# qfn-10-socket-pcb-mk-2_0_0.net
KiCad netlist of a schematic drawn in EAGLE
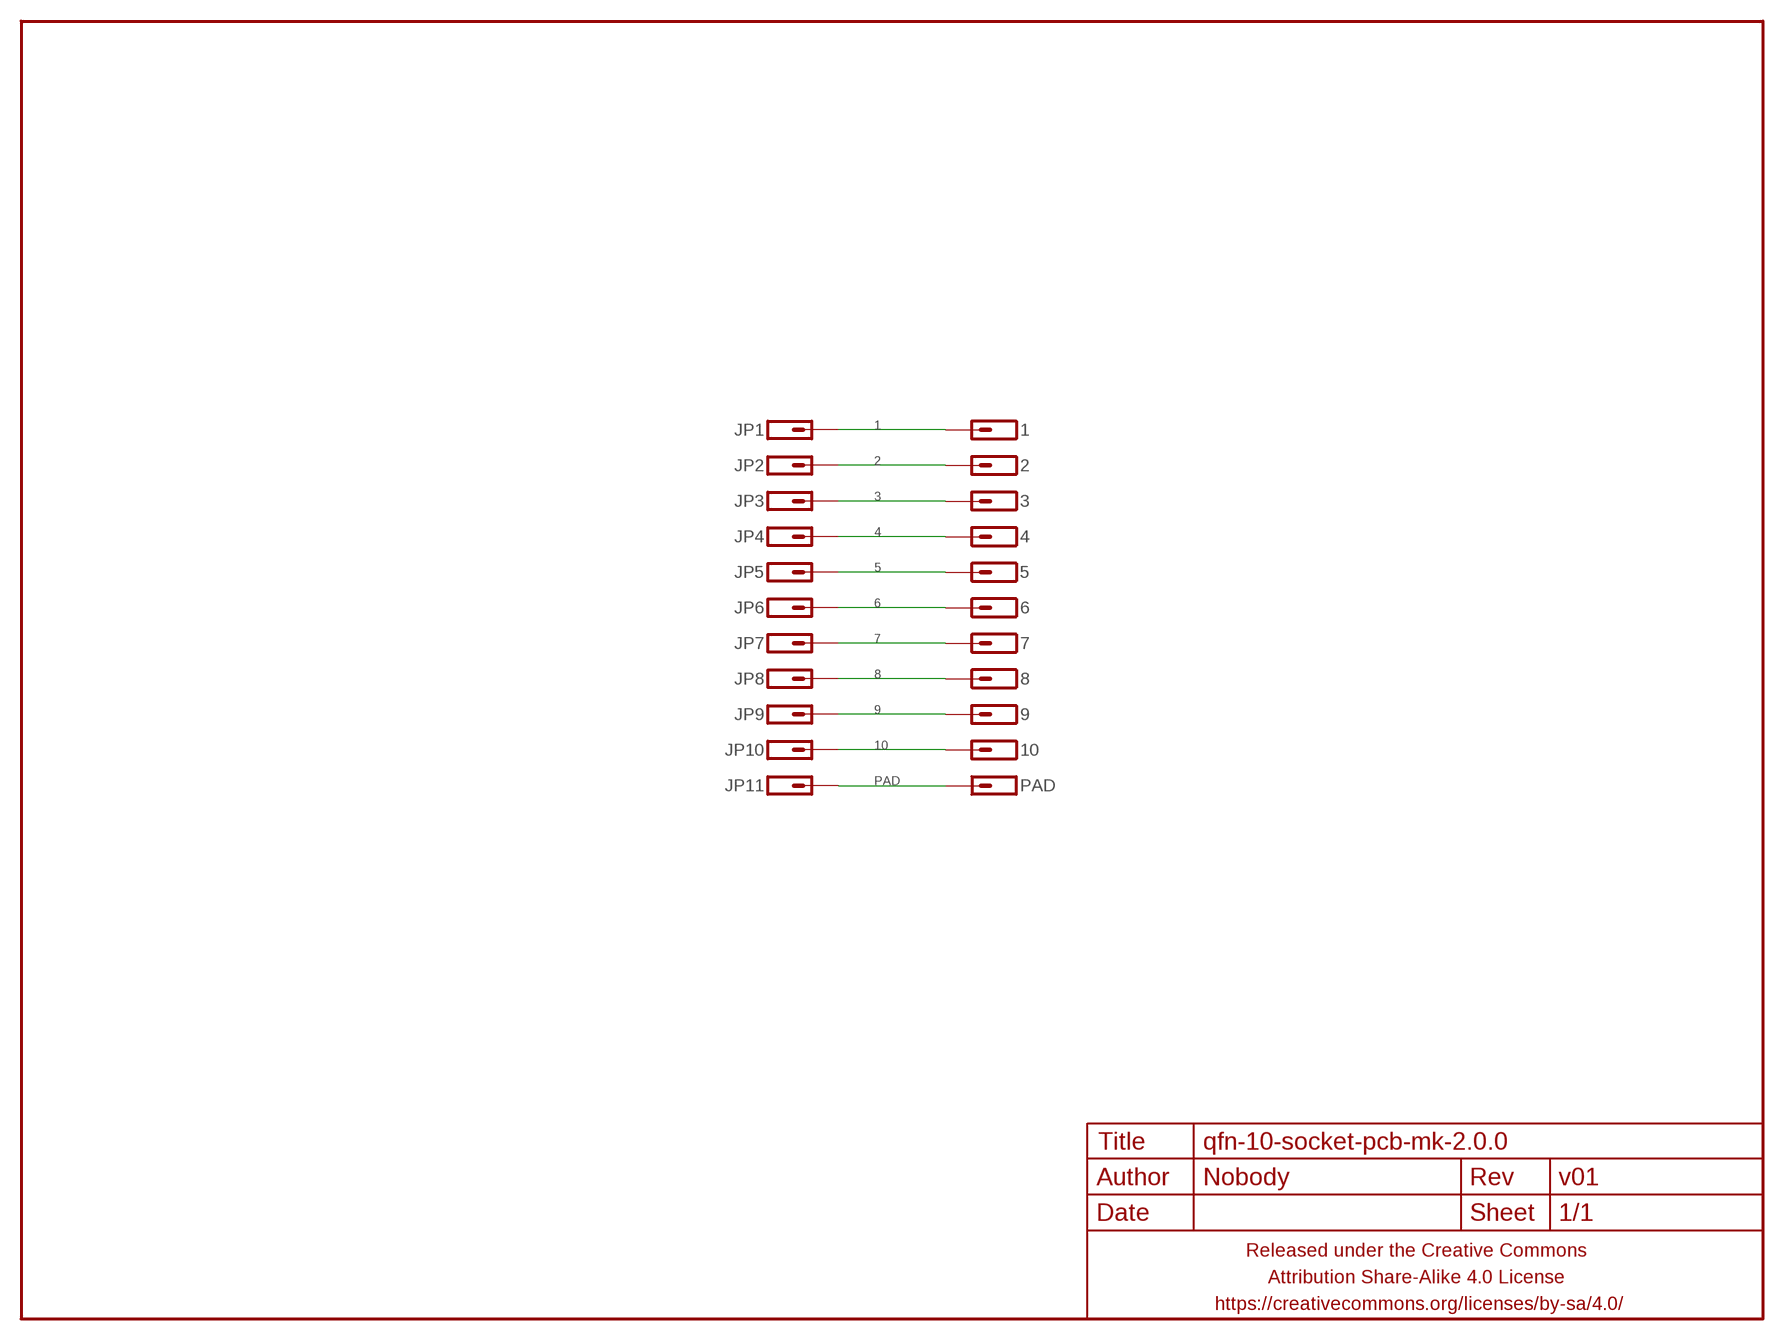
[diagram p0: schematic, sheet 1]

(export (version "E")
  (design (tool "Eeschema 10.0.6"))
  (components
    (comp (ref "1")
      (value "M01PTH")
      (footprint "eagle-import:1X01")
      (libsource (lib "eagle-import") (part "M01PTH"))
    )
    (comp (ref "2")
      (value "M01PTH")
      (footprint "eagle-import:1X01")
      (libsource (lib "eagle-import") (part "M01PTH"))
    )
    (comp (ref "3")
      (value "M01PTH")
      (footprint "eagle-import:1X01")
      (libsource (lib "eagle-import") (part "M01PTH"))
    )
    (comp (ref "4")
      (value "M01PTH")
      (footprint "eagle-import:1X01")
      (libsource (lib "eagle-import") (part "M01PTH"))
    )
    (comp (ref "5")
      (value "M01PTH")
      (footprint "eagle-import:1X01")
      (libsource (lib "eagle-import") (part "M01PTH"))
    )
    (comp (ref "6")
      (value "M01PTH")
      (footprint "eagle-import:1X01")
      (libsource (lib "eagle-import") (part "M01PTH"))
    )
    (comp (ref "7")
      (value "M01PTH")
      (footprint "eagle-import:1X01")
      (libsource (lib "eagle-import") (part "M01PTH"))
    )
    (comp (ref "8")
      (value "M01PTH")
      (footprint "eagle-import:1X01")
      (libsource (lib "eagle-import") (part "M01PTH"))
    )
    (comp (ref "9")
      (value "M01PTH")
      (footprint "eagle-import:1X01")
      (libsource (lib "eagle-import") (part "M01PTH"))
    )
    (comp (ref "10")
      (value "M01PTH")
      (footprint "eagle-import:1X01")
      (libsource (lib "eagle-import") (part "M01PTH"))
    )
    (comp (ref "FRAME1")
      (value "FRAME-LETTERNO_PACKAGE")
      (footprint "eagle-import:DUMMY")
      (fields (field (name "DESIGNER") "Nobody") (field (name "VERSION") "v01"))
      (libsource (lib "eagle-import") (part "FRAME-LETTERNO_PACKAGE"))
    )
    (comp (ref "JP1")
      (value "M01PTH-0.4MM")
      (footprint "eagle-import:1X01-0.4MM")
      (libsource (lib "eagle-import") (part "M01PTH-0.4MM"))
    )
    (comp (ref "JP2")
      (value "M01PTH-0.4MM")
      (footprint "eagle-import:1X01-0.4MM")
      (libsource (lib "eagle-import") (part "M01PTH-0.4MM"))
    )
    (comp (ref "JP3")
      (value "M01PTH-0.4MM")
      (footprint "eagle-import:1X01-0.4MM")
      (libsource (lib "eagle-import") (part "M01PTH-0.4MM"))
    )
    (comp (ref "JP4")
      (value "M01PTH-0.4MM")
      (footprint "eagle-import:1X01-0.4MM")
      (libsource (lib "eagle-import") (part "M01PTH-0.4MM"))
    )
    (comp (ref "JP5")
      (value "M01PTH-0.4MM")
      (footprint "eagle-import:1X01-0.4MM")
      (libsource (lib "eagle-import") (part "M01PTH-0.4MM"))
    )
    (comp (ref "JP6")
      (value "M01PTH-0.4MM")
      (footprint "eagle-import:1X01-0.4MM")
      (libsource (lib "eagle-import") (part "M01PTH-0.4MM"))
    )
    (comp (ref "JP7")
      (value "M01PTH-0.4MM")
      (footprint "eagle-import:1X01-0.4MM")
      (libsource (lib "eagle-import") (part "M01PTH-0.4MM"))
    )
    (comp (ref "JP8")
      (value "M01PTH-0.4MM")
      (footprint "eagle-import:1X01-0.4MM")
      (libsource (lib "eagle-import") (part "M01PTH-0.4MM"))
    )
    (comp (ref "JP9")
      (value "M01PTH-0.4MM")
      (footprint "eagle-import:1X01-0.4MM")
      (libsource (lib "eagle-import") (part "M01PTH-0.4MM"))
    )
    (comp (ref "JP10")
      (value "M01PTH-0.4MM")
      (footprint "eagle-import:1X01-0.4MM")
      (libsource (lib "eagle-import") (part "M01PTH-0.4MM"))
    )
    (comp (ref "JP11")
      (value "M01PTH")
      (footprint "eagle-import:1X01")
      (libsource (lib "eagle-import") (part "M01PTH"))
    )
    (comp (ref "PAD")
      (value "M01PTH-1MM-CIR-NS")
      (footprint "eagle-import:1X01-1MM-CIR-NS")
      (libsource (lib "eagle-import") (part "M01PTH-1MM-CIR-NS"))
    )
  )
  (nets
    (net (code "1") (name "/1") (class "Default")
      (node (ref "1") (pin "1") (pinfunction "1_1") (pintype "passive"))
      (node (ref "JP1") (pin "P$1") (pinfunction "1_P$1") (pintype "passive"))
    )
    (net (code "2") (name "/2") (class "Default")
      (node (ref "2") (pin "1") (pinfunction "1_1") (pintype "passive"))
      (node (ref "JP2") (pin "P$1") (pinfunction "1_P$1") (pintype "passive"))
    )
    (net (code "3") (name "/3") (class "Default")
      (node (ref "3") (pin "1") (pinfunction "1_1") (pintype "passive"))
      (node (ref "JP3") (pin "P$1") (pinfunction "1_P$1") (pintype "passive"))
    )
    (net (code "4") (name "/4") (class "Default")
      (node (ref "4") (pin "1") (pinfunction "1_1") (pintype "passive"))
      (node (ref "JP4") (pin "P$1") (pinfunction "1_P$1") (pintype "passive"))
    )
    (net (code "5") (name "/5") (class "Default")
      (node (ref "5") (pin "1") (pinfunction "1_1") (pintype "passive"))
      (node (ref "JP5") (pin "P$1") (pinfunction "1_P$1") (pintype "passive"))
    )
    (net (code "6") (name "/6") (class "Default")
      (node (ref "6") (pin "1") (pinfunction "1_1") (pintype "passive"))
      (node (ref "JP6") (pin "P$1") (pinfunction "1_P$1") (pintype "passive"))
    )
    (net (code "7") (name "/7") (class "Default")
      (node (ref "7") (pin "1") (pinfunction "1_1") (pintype "passive"))
      (node (ref "JP7") (pin "P$1") (pinfunction "1_P$1") (pintype "passive"))
    )
    (net (code "8") (name "/8") (class "Default")
      (node (ref "8") (pin "1") (pinfunction "1_1") (pintype "passive"))
      (node (ref "JP8") (pin "P$1") (pinfunction "1_P$1") (pintype "passive"))
    )
    (net (code "9") (name "/9") (class "Default")
      (node (ref "9") (pin "1") (pinfunction "1_1") (pintype "passive"))
      (node (ref "JP9") (pin "P$1") (pinfunction "1_P$1") (pintype "passive"))
    )
    (net (code "10") (name "/10") (class "Default")
      (node (ref "10") (pin "1") (pinfunction "1_1") (pintype "passive"))
      (node (ref "JP10") (pin "P$1") (pinfunction "1_P$1") (pintype "passive"))
    )
    (net (code "11") (name "/PAD") (class "Default")
      (node (ref "JP11") (pin "1") (pinfunction "1_1") (pintype "passive"))
      (node (ref "PAD") (pin "1") (pinfunction "1_1") (pintype "passive"))
    )
  )
)
